# Esquem_tico_e_Layout_-_Shield_Display.net
KiCad netlist of a schematic drawn in EasyEDA Pro
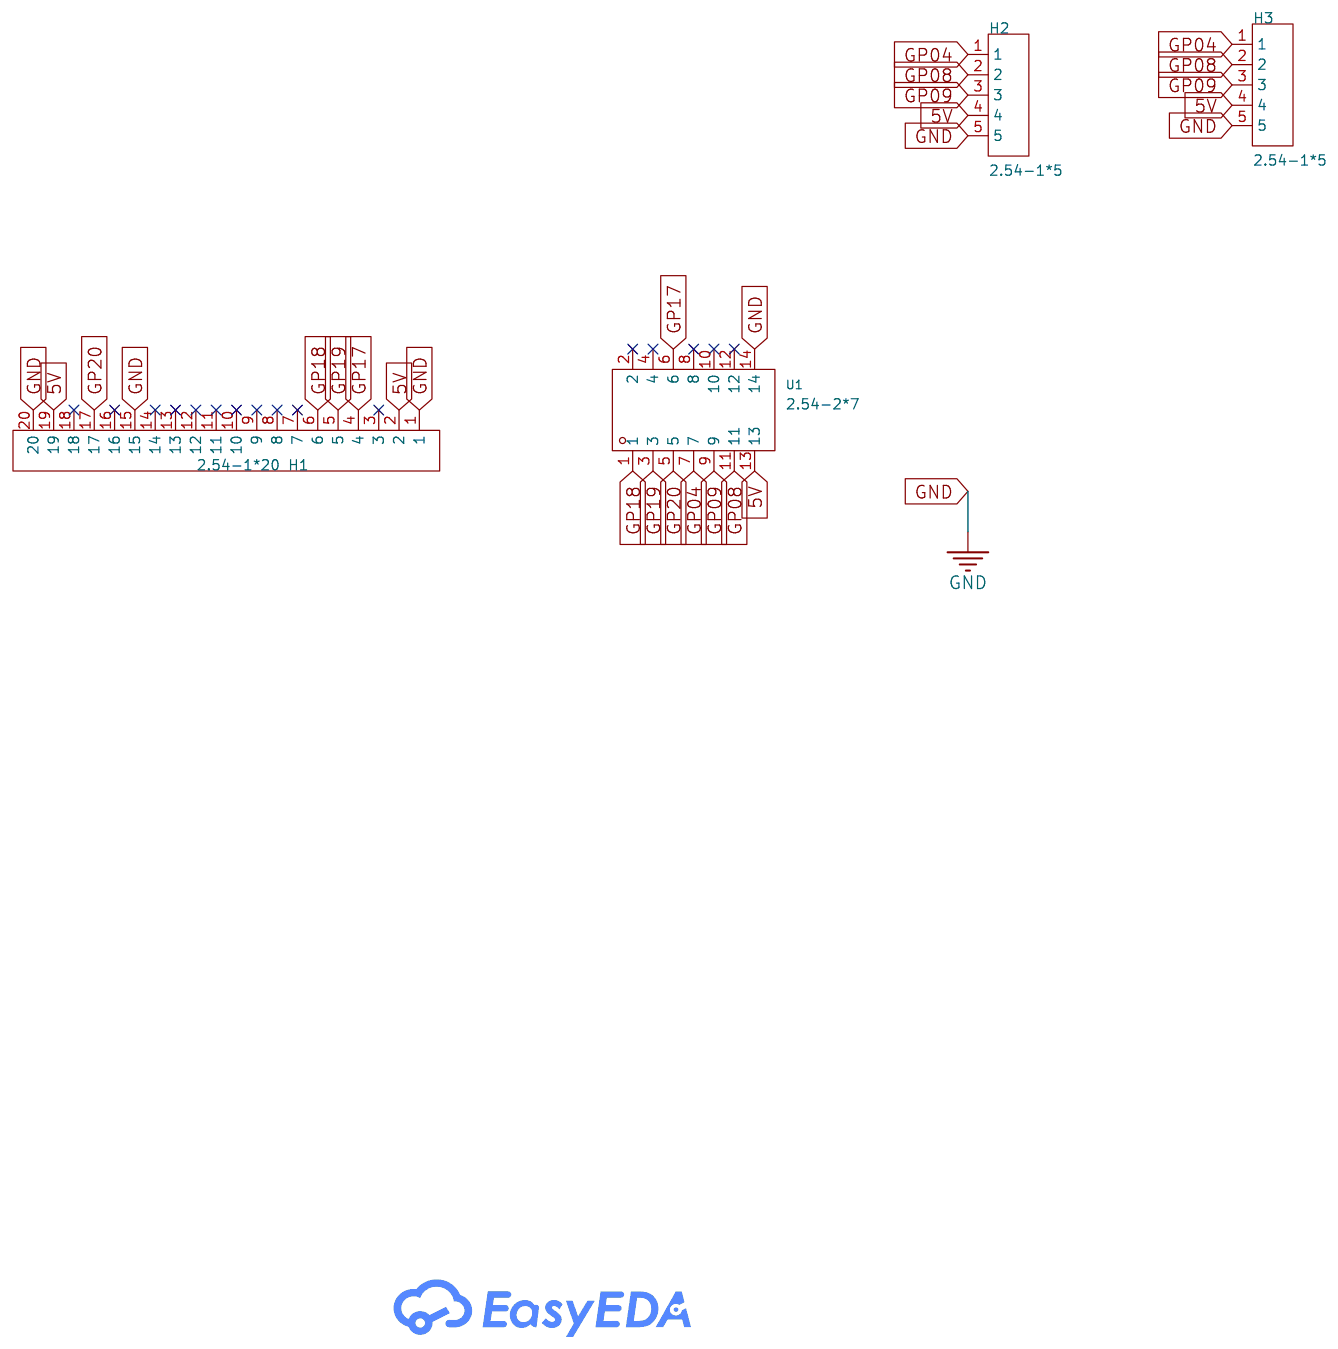
[diagram p0: schematic sheet]

(export (version "E")
  (design (tool "Eeschema 10.0.6"))
  (components
    (comp (ref "H1")
      (value "2.54-1*20")
      (footprint "easyedapro:HDR-TH_20P-P2.54-V-M")
      (description "Pin Structure:1x20P Pitch:2.54mm Number of Rows:1 Number of Pins:20P")
      (fields (field (name "Manufacturer") "ZHOURI(洲日)"))
      (libsource (lib "easyedapro") (part "2.54-1*20"))
    )
    (comp (ref "H2")
      (value "2.54-1*5")
      (footprint "easyedapro:HDR-TH_5P-P2.54-V-M")
      (description "Pin Structure:1x5P Pitch:2.54mm Number of Rows:1 Number of Pins:5P")
      (fields (field (name "Manufacturer") "ZHOURI(洲日)"))
      (libsource (lib "easyedapro") (part "2.54-1*5"))
    )
    (comp (ref "H3")
      (value "2.54-1*5")
      (footprint "easyedapro:HDR-TH_5P-P2.54-V-M")
      (description "Pin Structure:1x5P Pitch:2.54mm Number of Rows:1 Number of Pins:5P")
      (fields (field (name "Manufacturer") "ZHOURI(洲日)"))
      (libsource (lib "easyedapro") (part "2.54-1*5"))
    )
    (comp (ref "U1")
      (value "2.54-2*7")
      (footprint "easyedapro:HDR-TH_14P-P2.54-V-F-R2-C7-S2.54")
      (description "Pin Structure:2x7P Pitch:2.54mm Number of Rows:2 Number of Pins:14P")
      (fields (field (name "Manufacturer") "ZHOURI(洲日)"))
      (libsource (lib "easyedapro") (part "2.54-2*7"))
    )
  )
  (nets
    (net (code "1") (name "5V") (class "Default")
      (node (ref "H1") (pin "19") (pinfunction "19_19") (pintype "unspecified"))
      (node (ref "H1") (pin "2") (pinfunction "2_2") (pintype "unspecified"))
      (node (ref "H2") (pin "4") (pinfunction "4_4") (pintype "unspecified"))
      (node (ref "H3") (pin "4") (pinfunction "4_4") (pintype "unspecified"))
      (node (ref "U1") (pin "13") (pinfunction "13_13") (pintype "input"))
    )
    (net (code "2") (name "GND") (class "Default")
      (node (ref "H1") (pin "1") (pinfunction "1_1") (pintype "unspecified"))
      (node (ref "H1") (pin "15") (pinfunction "15_15") (pintype "unspecified"))
      (node (ref "H1") (pin "20") (pinfunction "20_20") (pintype "unspecified"))
      (node (ref "H2") (pin "5") (pinfunction "5_5") (pintype "unspecified"))
      (node (ref "H3") (pin "5") (pinfunction "5_5") (pintype "unspecified"))
      (node (ref "U1") (pin "14") (pinfunction "14_14") (pintype "input"))
    )
    (net (code "3") (name "GP04") (class "Default")
      (node (ref "H2") (pin "1") (pinfunction "1_1") (pintype "unspecified"))
      (node (ref "H3") (pin "1") (pinfunction "1_1") (pintype "unspecified"))
      (node (ref "U1") (pin "7") (pinfunction "7_7") (pintype "input"))
    )
    (net (code "4") (name "GP08") (class "Default")
      (node (ref "H2") (pin "2") (pinfunction "2_2") (pintype "unspecified"))
      (node (ref "H3") (pin "2") (pinfunction "2_2") (pintype "unspecified"))
      (node (ref "U1") (pin "11") (pinfunction "11_11") (pintype "input"))
    )
    (net (code "5") (name "GP09") (class "Default")
      (node (ref "H2") (pin "3") (pinfunction "3_3") (pintype "unspecified"))
      (node (ref "H3") (pin "3") (pinfunction "3_3") (pintype "unspecified"))
      (node (ref "U1") (pin "9") (pinfunction "9_9") (pintype "input"))
    )
    (net (code "6") (name "GP17") (class "Default")
      (node (ref "H1") (pin "4") (pinfunction "4_4") (pintype "unspecified"))
      (node (ref "U1") (pin "6") (pinfunction "6_6") (pintype "input"))
    )
    (net (code "7") (name "GP18") (class "Default")
      (node (ref "H1") (pin "6") (pinfunction "6_6") (pintype "unspecified"))
      (node (ref "U1") (pin "1") (pinfunction "1_1") (pintype "input"))
    )
    (net (code "8") (name "GP19") (class "Default")
      (node (ref "H1") (pin "5") (pinfunction "5_5") (pintype "unspecified"))
      (node (ref "U1") (pin "3") (pinfunction "3_3") (pintype "input"))
    )
    (net (code "9") (name "GP20") (class "Default")
      (node (ref "H1") (pin "17") (pinfunction "17_17") (pintype "unspecified"))
      (node (ref "U1") (pin "5") (pinfunction "5_5") (pintype "input"))
    )
    (net (code "10") (name "unconnected-(H1-Pad3)") (class "Default")
      (node (ref "H1") (pin "3") (pinfunction "3_3") (pintype "unspecified+no_connect"))
    )
    (net (code "11") (name "unconnected-(H1-Pad7)") (class "Default")
      (node (ref "H1") (pin "7") (pinfunction "7_7") (pintype "unspecified+no_connect"))
    )
    (net (code "12") (name "unconnected-(H1-Pad8)") (class "Default")
      (node (ref "H1") (pin "8") (pinfunction "8_8") (pintype "unspecified+no_connect"))
    )
    (net (code "13") (name "unconnected-(H1-Pad9)") (class "Default")
      (node (ref "H1") (pin "9") (pinfunction "9_9") (pintype "unspecified+no_connect"))
    )
    (net (code "14") (name "unconnected-(H1-Pad10)") (class "Default")
      (node (ref "H1") (pin "10") (pinfunction "10_10") (pintype "unspecified+no_connect"))
    )
    (net (code "15") (name "unconnected-(H1-Pad11)") (class "Default")
      (node (ref "H1") (pin "11") (pinfunction "11_11") (pintype "unspecified+no_connect"))
    )
    (net (code "16") (name "unconnected-(H1-Pad12)") (class "Default")
      (node (ref "H1") (pin "12") (pinfunction "12_12") (pintype "unspecified+no_connect"))
    )
    (net (code "17") (name "unconnected-(H1-Pad13)") (class "Default")
      (node (ref "H1") (pin "13") (pinfunction "13_13") (pintype "unspecified+no_connect"))
    )
    (net (code "18") (name "unconnected-(H1-Pad14)") (class "Default")
      (node (ref "H1") (pin "14") (pinfunction "14_14") (pintype "unspecified+no_connect"))
    )
    (net (code "19") (name "unconnected-(H1-Pad16)") (class "Default")
      (node (ref "H1") (pin "16") (pinfunction "16_16") (pintype "unspecified+no_connect"))
    )
    (net (code "20") (name "unconnected-(H1-Pad18)") (class "Default")
      (node (ref "H1") (pin "18") (pinfunction "18_18") (pintype "unspecified+no_connect"))
    )
    (net (code "21") (name "unconnected-(U1-Pad2)") (class "Default")
      (node (ref "U1") (pin "2") (pinfunction "2_2") (pintype "input+no_connect"))
    )
    (net (code "22") (name "unconnected-(U1-Pad4)") (class "Default")
      (node (ref "U1") (pin "4") (pinfunction "4_4") (pintype "input+no_connect"))
    )
    (net (code "23") (name "unconnected-(U1-Pad8)") (class "Default")
      (node (ref "U1") (pin "8") (pinfunction "8_8") (pintype "input+no_connect"))
    )
    (net (code "24") (name "unconnected-(U1-Pad10)") (class "Default")
      (node (ref "U1") (pin "10") (pinfunction "10_10") (pintype "input+no_connect"))
    )
    (net (code "25") (name "unconnected-(U1-Pad12)") (class "Default")
      (node (ref "U1") (pin "12") (pinfunction "12_12") (pintype "input+no_connect"))
    )
  )
)
